# Connectors.net
KiCad netlist of a schematic drawn in Altium Designer
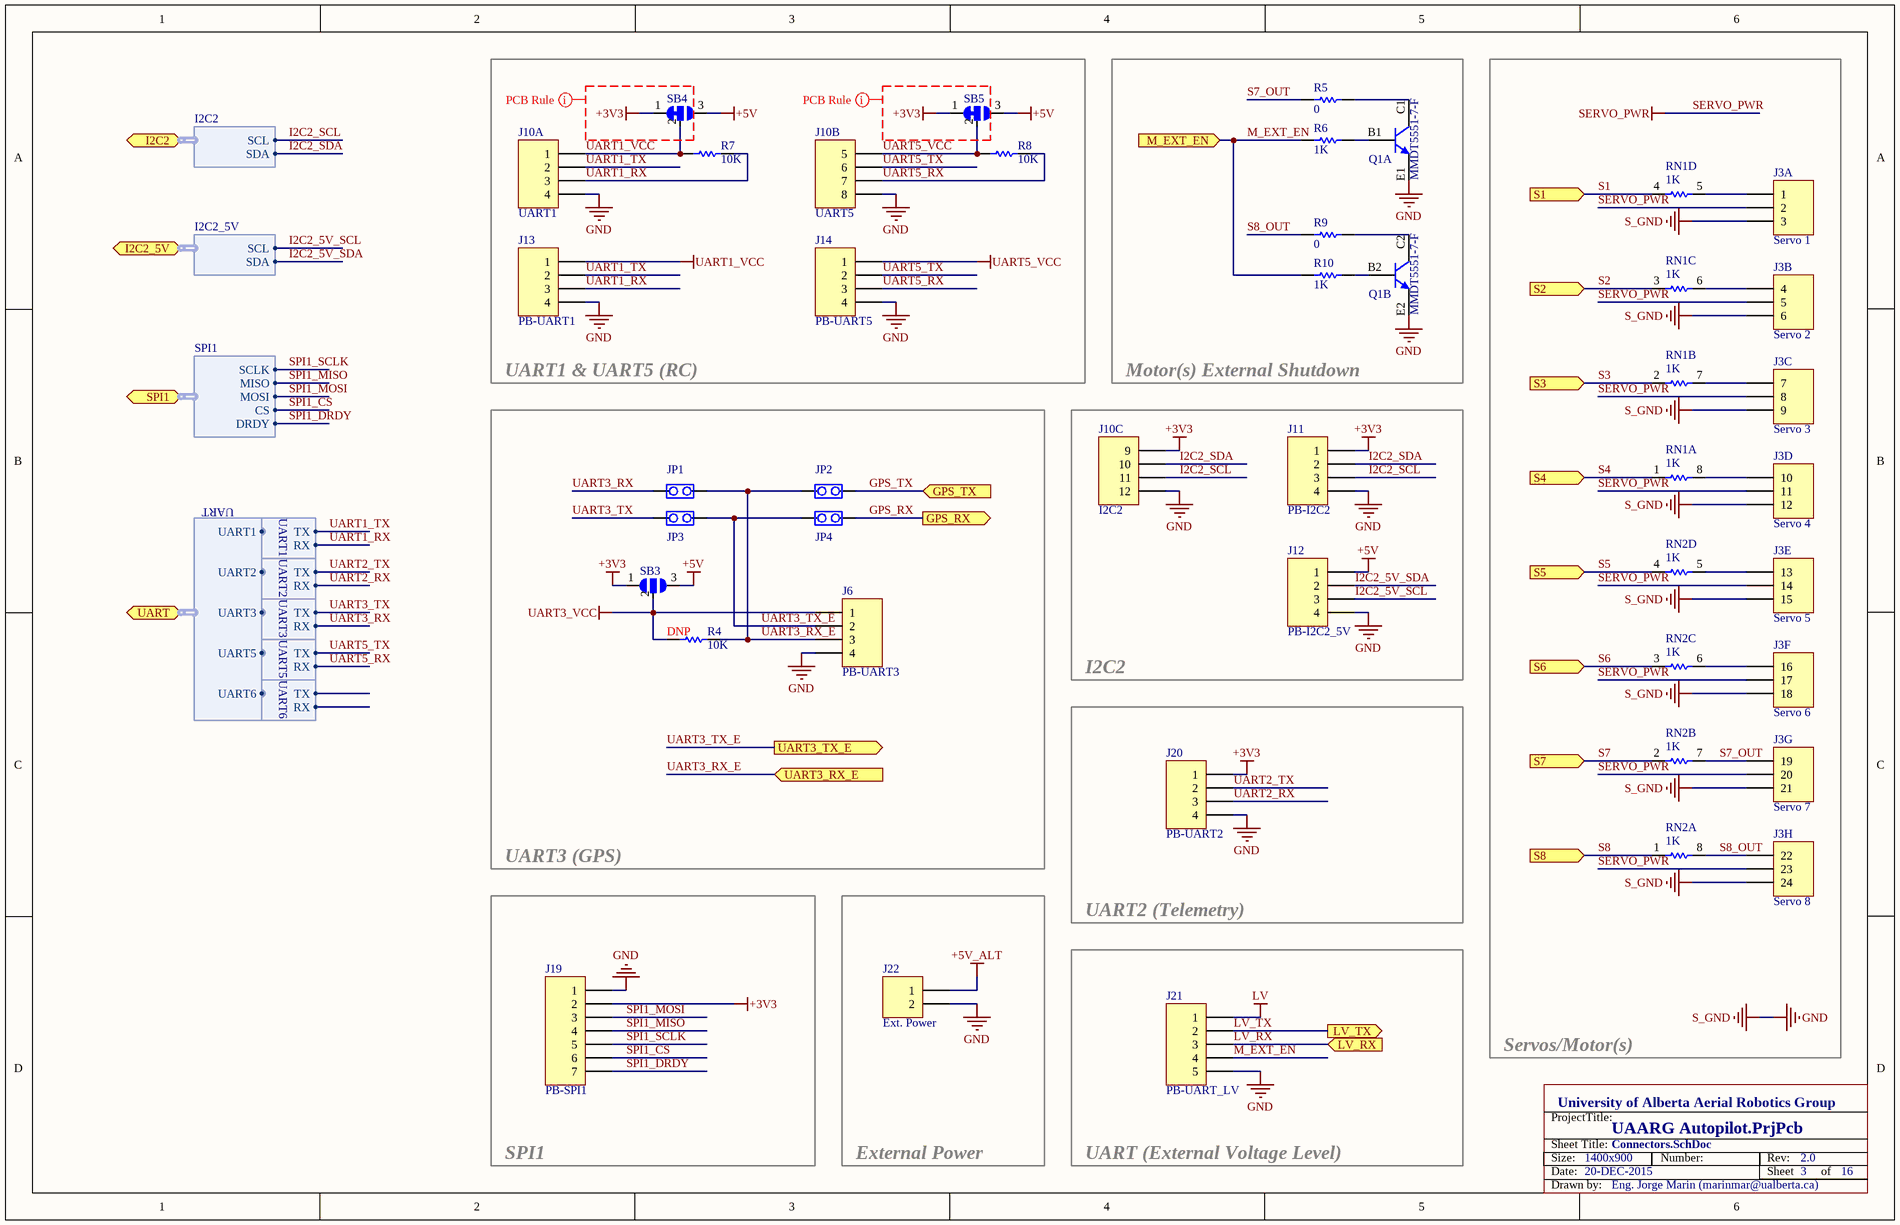
[diagram p0: Connectors.SchDoc]

(export (version "E")
  (design (tool "Eeschema 10.0.6"))
  (components
    (comp (ref "J3")
      (value "Servo")
      (footprint "HDR_3x08_RA")
      (description "Header, 24-Pin")
      (libsource (lib "UAARG Autopilot") (part "Header 3X08 RA"))
    )
    (comp (ref "J6")
      (value "PB-UART3")
      (footprint "PICOBLADE_1X04_VERT_SMD")
      (description "Header, 4-Pin")
      (fields
        (field (name "MANUFACTURER") "Molex, LLC")
        (field (name "MANUFACTURER PART NUMBER") "0533980471")
      )
      (libsource (lib "") (part "Header 4_1"))
    )
    (comp (ref "J10")
      (value "Header")
      (footprint "HDR_3x04_RA")
      (description "Header, 12-Pin")
      (libsource (lib "UAARG Autopilot") (part "Header 3X04 RA"))
    )
    (comp (ref "J11")
      (value "PB-I2C2")
      (footprint "PICOBLADE_1X04_VERT_SMD")
      (description "Header, 4-Pin")
      (fields
        (field (name "MANUFACTURER") "Molex, LLC")
        (field (name "MANUFACTURER PART NUMBER") "0533980471")
      )
      (libsource (lib "Miscellaneous Connectors") (part "Header 4"))
    )
    (comp (ref "J12")
      (value "PB-I2C2_5V")
      (footprint "PICOBLADE_1X04_VERT_SMD")
      (description "Header, 4-Pin")
      (fields
        (field (name "MANUFACTURER") "Molex, LLC")
        (field (name "MANUFACTURER PART NUMBER") "0533980471")
      )
      (libsource (lib "Miscellaneous Connectors") (part "Header 4"))
    )
    (comp (ref "J13")
      (value "PB-UART1")
      (footprint "PICOBLADE_1X04_VERT_SMD")
      (description "Header, 4-Pin")
      (fields
        (field (name "MANUFACTURER") "Molex, LLC")
        (field (name "MANUFACTURER PART NUMBER") "0533980471")
      )
      (libsource (lib "Miscellaneous Connectors") (part "Header 4"))
    )
    (comp (ref "J14")
      (value "PB-UART5")
      (footprint "PICOBLADE_1X04_VERT_SMD")
      (description "Header, 4-Pin")
      (fields
        (field (name "MANUFACTURER") "Molex, LLC")
        (field (name "MANUFACTURER PART NUMBER") "0533980471")
      )
      (libsource (lib "Miscellaneous Connectors") (part "Header 4"))
    )
    (comp (ref "J19")
      (value "PB-SPI1")
      (footprint "PICOBLADE_1X07_VERT_SMD")
      (description "Header, 7-Pin")
      (fields
        (field (name "MANUFACTURER") "Molex, LLC")
        (field (name "MANUFACTURER PART NUMBER") "0533980771")
      )
      (libsource (lib "Miscellaneous Connectors") (part "Header 7"))
    )
    (comp (ref "J20")
      (value "PB-UART2")
      (footprint "PICOBLADE_1X04_VERT_SMD")
      (description "Header, 4-Pin")
      (fields
        (field (name "MANUFACTURER") "Molex, LLC")
        (field (name "MANUFACTURER PART NUMBER") "0533980471")
      )
      (libsource (lib "Miscellaneous Connectors") (part "Header 4"))
    )
    (comp (ref "J21")
      (value "PB-UART_LV")
      (footprint "PICOBLADE_1X05_VERT_SMD")
      (description "Header, 5-Pin")
      (fields
        (field (name "MANUFACTURER PART NUMBER") "0533980571")
        (field (name "MANUFACTURER") "Molex, LLC")
      )
      (libsource (lib "Miscellaneous Connectors") (part "Header 5"))
    )
    (comp (ref "J22")
      (value "Ext. Power")
      (footprint "HDR_1x02")
      (description "Header, 2-Pin")
      (libsource (lib "Miscellaneous Connectors") (part "Header 2"))
    )
    (comp (ref "JP1") (value "Jumper") (footprint "HDR_1x02_JMP") (libsource (lib "") (part "Jumper_1")))
    (comp (ref "JP2")
      (value "Jumper")
      (footprint "HDR_1x02_JMP")
      (libsource (lib "UAARG Autopilot") (part "Jumper"))
    )
    (comp (ref "JP3") (value "Jumper") (footprint "HDR_1x02_JMP") (libsource (lib "") (part "Jumper_1")))
    (comp (ref "JP4")
      (value "Jumper")
      (footprint "HDR_1x02_JMP")
      (libsource (lib "UAARG Autopilot") (part "Jumper"))
    )
    (comp (ref "Q1")
      (value "BJT NPN DUAL")
      (footprint "SOT363-6")
      (description "NPN General Purpose Amplifier")
      (fields
        (field (name "MANUFACTURER PART NUMBER") "MMDT5551-7-F")
        (field (name "MANUFACTURER") "Diodes Incorporated")
      )
      (libsource (lib "UAARG Autopilot") (part "BJT NPN DUAL"))
    )
    (comp (ref "R4")
      (value "10K")
      (footprint "RES_0402[1005M]")
      (description "Resistor")
      (fields
        (field (name "MANUFACTURER") "Yageo")
        (field (name "MANUFACTURER PART NUMBER") "RC0402FR-0710KL")
        (field (name "NOTE") "DNP")
      )
      (libsource (lib "UAARG Autopilot") (part "RES"))
    )
    (comp (ref "R5")
      (value "0")
      (footprint "JUMPER_RES_0402")
      (description "Resistor")
      (fields
        (field (name "MANUFACTURER PART NUMBER") "RC0402JR-070RL")
        (field (name "MANUFACTURER") "Yageo")
      )
      (libsource (lib "UAARG Autopilot") (part "RES"))
    )
    (comp (ref "R6")
      (value "1K")
      (footprint "RES_0402[1005M]")
      (description "Resistor")
      (fields
        (field (name "MANUFACTURER") "Yageo")
        (field (name "MANUFACTURER PART NUMBER") "RC0402FR-071KL")
      )
      (libsource (lib "UAARG Autopilot") (part "RES"))
    )
    (comp (ref "R7")
      (value "10K")
      (footprint "RES_0402[1005M]")
      (description "Resistor")
      (fields
        (field (name "MANUFACTURER") "Yageo")
        (field (name "MANUFACTURER PART NUMBER") "RC0402FR-0710KL")
      )
      (libsource (lib "UAARG Autopilot") (part "RES"))
    )
    (comp (ref "R8")
      (value "10K")
      (footprint "RES_0402[1005M]")
      (description "Resistor")
      (fields
        (field (name "MANUFACTURER") "Yageo")
        (field (name "MANUFACTURER PART NUMBER") "RC0402FR-0710KL")
      )
      (libsource (lib "UAARG Autopilot") (part "RES"))
    )
    (comp (ref "R9")
      (value "0")
      (footprint "JUMPER_RES_0402")
      (description "Resistor")
      (fields
        (field (name "MANUFACTURER PART NUMBER") "RC0402JR-070RL")
        (field (name "MANUFACTURER") "Yageo")
      )
      (libsource (lib "UAARG Autopilot") (part "RES"))
    )
    (comp (ref "R10")
      (value "1K")
      (footprint "RES_0402[1005M]")
      (description "Resistor")
      (fields
        (field (name "MANUFACTURER") "Yageo")
        (field (name "MANUFACTURER PART NUMBER") "RC0402FR-071KL")
      )
      (libsource (lib "UAARG Autopilot") (part "RES"))
    )
    (comp (ref "RN1")
      (value "1K")
      (footprint "RES ARRAY SMD")
      (description "Isolated Resistor Network")
      (fields
        (field (name "MANUFACTURER PART NUMBER") "YC164-JR-071KL")
        (field (name "MANUFACTURER") "Yageo")
      )
      (libsource (lib "UAARG Autopilot") (part "Res Network 1"))
    )
    (comp (ref "RN2")
      (value "1K")
      (footprint "RES ARRAY SMD")
      (description "Isolated Resistor Network")
      (fields
        (field (name "MANUFACTURER PART NUMBER") "YC164-JR-071KL")
        (field (name "MANUFACTURER") "Yageo")
      )
      (libsource (lib "UAARG Autopilot") (part "Res Network 1"))
    )
    (comp (ref "SB3")
      (value "SMD Jumper 1")
      (footprint "SMD JUMPER 1")
      (description "SMD Jumper 3 positions. Open")
      (libsource (lib "UAARG Autopilot") (part "SMD Jumper 1"))
    )
    (comp (ref "SB4")
      (value "SMD Jumper 2")
      (footprint "SMD JUMPER 2")
      (description "SMD Jumper 3 positions. Closed")
      (libsource (lib "UAARG Autopilot") (part "SMD Jumper 2"))
    )
    (comp (ref "SB5")
      (value "SMD Jumper 2")
      (footprint "SMD JUMPER 2")
      (description "SMD Jumper 3 positions. Closed")
      (libsource (lib "UAARG Autopilot") (part "SMD Jumper 2"))
    )
  )
  (nets
    (net (code "5") (name "+3V3") (class "Default")
      (node (ref "J10") (pin "9") (pinfunction "9_9") (pintype "passive"))
      (node (ref "J11") (pin "1") (pinfunction "1_1") (pintype "passive"))
      (node (ref "J19") (pin "2") (pinfunction "2_2") (pintype "passive"))
      (node (ref "J20") (pin "1") (pinfunction "1_1") (pintype "passive"))
      (node (ref "SB3") (pin "1") (pinfunction "1_1") (pintype "passive"))
      (node (ref "SB4") (pin "1") (pinfunction "1_1") (pintype "passive"))
      (node (ref "SB5") (pin "1") (pinfunction "1_1") (pintype "passive"))
    )
    (net (code "6") (name "+5V") (class "Default")
      (node (ref "J12") (pin "1") (pinfunction "1_1") (pintype "passive"))
      (node (ref "SB3") (pin "3") (pinfunction "3_3") (pintype "passive"))
      (node (ref "SB4") (pin "3") (pinfunction "3_3") (pintype "passive"))
      (node (ref "SB5") (pin "3") (pinfunction "3_3") (pintype "passive"))
    )
    (net (code "7") (name "+5V_ALT") (class "Default")
      (node (ref "J22") (pin "1") (pinfunction "1_1") (pintype "passive"))
    )
    (net (code "8") (name "/GPS_RX") (class "Default")
      (node (ref "JP4") (pin "1") (pinfunction "1_1") (pintype "passive"))
    )
    (net (code "9") (name "/GPS_TX") (class "Default")
      (node (ref "JP2") (pin "1") (pinfunction "1_1") (pintype "passive"))
    )
    (net (code "10") (name "/I2C2_5V_SCL") (class "Default")
      (node (ref "J12") (pin "3") (pinfunction "3_3") (pintype "passive"))
    )
    (net (code "11") (name "/I2C2_5V_SDA") (class "Default")
      (node (ref "J12") (pin "2") (pinfunction "2_2") (pintype "passive"))
    )
    (net (code "12") (name "/I2C2_SCL") (class "Default")
      (node (ref "J10") (pin "11") (pinfunction "11_11") (pintype "passive"))
      (node (ref "J11") (pin "3") (pinfunction "3_3") (pintype "passive"))
    )
    (net (code "13") (name "/I2C2_SDA") (class "Default")
      (node (ref "J10") (pin "10") (pinfunction "10_10") (pintype "passive"))
      (node (ref "J11") (pin "2") (pinfunction "2_2") (pintype "passive"))
    )
    (net (code "14") (name "/LV_RX") (class "Default")
      (node (ref "J21") (pin "3") (pinfunction "3_3") (pintype "passive"))
    )
    (net (code "15") (name "/LV_TX") (class "Default")
      (node (ref "J21") (pin "2") (pinfunction "2_2") (pintype "passive"))
    )
    (net (code "16") (name "/M_EXT_EN") (class "Default")
      (node (ref "J21") (pin "4") (pinfunction "4_4") (pintype "passive"))
      (node (ref "R10") (pin "2") (pinfunction "2_2") (pintype "passive"))
      (node (ref "R6") (pin "2") (pinfunction "2_2") (pintype "passive"))
    )
    (net (code "17") (name "/S1") (class "Default")
      (node (ref "RN1") (pin "4") (pinfunction "4_4") (pintype "passive"))
    )
    (net (code "18") (name "/S2") (class "Default")
      (node (ref "RN1") (pin "3") (pinfunction "3_3") (pintype "passive"))
    )
    (net (code "19") (name "/S3") (class "Default")
      (node (ref "RN1") (pin "2") (pinfunction "2_2") (pintype "passive"))
    )
    (net (code "20") (name "/S4") (class "Default")
      (node (ref "RN1") (pin "1") (pinfunction "1_1") (pintype "passive"))
    )
    (net (code "21") (name "/S5") (class "Default")
      (node (ref "RN2") (pin "4") (pinfunction "4_4") (pintype "passive"))
    )
    (net (code "22") (name "/S6") (class "Default")
      (node (ref "RN2") (pin "3") (pinfunction "3_3") (pintype "passive"))
    )
    (net (code "23") (name "/S7") (class "Default")
      (node (ref "RN2") (pin "2") (pinfunction "2_2") (pintype "passive"))
    )
    (net (code "24") (name "/S7_OUT") (class "Default")
      (node (ref "J3") (pin "19") (pinfunction "19_19") (pintype "passive"))
      (node (ref "R5") (pin "2") (pinfunction "2_2") (pintype "passive"))
      (node (ref "RN2") (pin "7") (pinfunction "7_7") (pintype "passive"))
    )
    (net (code "25") (name "/S8") (class "Default")
      (node (ref "RN2") (pin "1") (pinfunction "1_1") (pintype "passive"))
    )
    (net (code "26") (name "/S8_OUT") (class "Default")
      (node (ref "J3") (pin "22") (pinfunction "22_22") (pintype "passive"))
      (node (ref "R9") (pin "2") (pinfunction "2_2") (pintype "passive"))
      (node (ref "RN2") (pin "8") (pinfunction "8_8") (pintype "passive"))
    )
    (net (code "27") (name "/SPI1_CS") (class "Default")
      (node (ref "J19") (pin "6") (pinfunction "6_6") (pintype "passive"))
    )
    (net (code "28") (name "/SPI1_DRDY") (class "Default")
      (node (ref "J19") (pin "7") (pinfunction "7_7") (pintype "passive"))
    )
    (net (code "29") (name "/SPI1_MISO") (class "Default")
      (node (ref "J19") (pin "4") (pinfunction "4_4") (pintype "passive"))
    )
    (net (code "30") (name "/SPI1_MOSI") (class "Default")
      (node (ref "J19") (pin "3") (pinfunction "3_3") (pintype "passive"))
    )
    (net (code "31") (name "/SPI1_SCLK") (class "Default")
      (node (ref "J19") (pin "5") (pinfunction "5_5") (pintype "passive"))
    )
    (net (code "32") (name "/UART1_RX") (class "Default")
      (node (ref "J10") (pin "3") (pinfunction "3_3") (pintype "passive"))
      (node (ref "J13") (pin "3") (pinfunction "3_3") (pintype "passive"))
      (node (ref "R7") (pin "1") (pinfunction "1_1") (pintype "passive"))
    )
    (net (code "33") (name "/UART1_TX") (class "Default")
      (node (ref "J10") (pin "2") (pinfunction "2_2") (pintype "passive"))
      (node (ref "J13") (pin "2") (pinfunction "2_2") (pintype "passive"))
    )
    (net (code "34") (name "/UART2_RX") (class "Default")
      (node (ref "J20") (pin "3") (pinfunction "3_3") (pintype "passive"))
    )
    (net (code "35") (name "/UART2_TX") (class "Default")
      (node (ref "J20") (pin "2") (pinfunction "2_2") (pintype "passive"))
    )
    (net (code "36") (name "/UART3_RX") (class "Default")
      (node (ref "JP1") (pin "1") (pinfunction "1_1") (pintype "passive"))
    )
    (net (code "37") (name "/UART3_RX_E") (class "Default")
      (node (ref "J6") (pin "3") (pinfunction "3_3") (pintype "passive"))
      (node (ref "JP1") (pin "2") (pinfunction "2_2") (pintype "passive"))
      (node (ref "JP2") (pin "2") (pinfunction "2_2") (pintype "passive"))
      (node (ref "R4") (pin "1") (pinfunction "1_1") (pintype "passive"))
    )
    (net (code "38") (name "/UART3_TX") (class "Default")
      (node (ref "JP3") (pin "1") (pinfunction "1_1") (pintype "passive"))
    )
    (net (code "39") (name "/UART3_TX_E") (class "Default")
      (node (ref "J6") (pin "2") (pinfunction "2_2") (pintype "passive"))
      (node (ref "JP3") (pin "2") (pinfunction "2_2") (pintype "passive"))
      (node (ref "JP4") (pin "2") (pinfunction "2_2") (pintype "passive"))
    )
    (net (code "40") (name "/UART5_RX") (class "Default")
      (node (ref "J10") (pin "7") (pinfunction "7_7") (pintype "passive"))
      (node (ref "J14") (pin "3") (pinfunction "3_3") (pintype "passive"))
      (node (ref "R8") (pin "1") (pinfunction "1_1") (pintype "passive"))
    )
    (net (code "41") (name "/UART5_TX") (class "Default")
      (node (ref "J10") (pin "6") (pinfunction "6_6") (pintype "passive"))
      (node (ref "J14") (pin "2") (pinfunction "2_2") (pintype "passive"))
    )
    (net (code "46") (name "GND") (class "Default")
      (node (ref "J10") (pin "12") (pinfunction "12_12") (pintype "passive"))
      (node (ref "J10") (pin "4") (pinfunction "4_4") (pintype "passive"))
      (node (ref "J10") (pin "8") (pinfunction "8_8") (pintype "passive"))
      (node (ref "J11") (pin "4") (pinfunction "4_4") (pintype "passive"))
      (node (ref "J12") (pin "4") (pinfunction "4_4") (pintype "passive"))
      (node (ref "J13") (pin "4") (pinfunction "4_4") (pintype "passive"))
      (node (ref "J14") (pin "4") (pinfunction "4_4") (pintype "passive"))
      (node (ref "J19") (pin "1") (pinfunction "1_1") (pintype "passive"))
      (node (ref "J20") (pin "4") (pinfunction "4_4") (pintype "passive"))
      (node (ref "J21") (pin "5") (pinfunction "5_5") (pintype "passive"))
      (node (ref "J22") (pin "2") (pinfunction "2_2") (pintype "passive"))
      (node (ref "J3") (pin "12") (pinfunction "12_12") (pintype "passive"))
      (node (ref "J3") (pin "15") (pinfunction "15_15") (pintype "passive"))
      (node (ref "J3") (pin "18") (pinfunction "18_18") (pintype "passive"))
      (node (ref "J3") (pin "21") (pinfunction "21_21") (pintype "passive"))
      (node (ref "J3") (pin "24") (pinfunction "24_24") (pintype "passive"))
      (node (ref "J3") (pin "3") (pinfunction "3_3") (pintype "passive"))
      (node (ref "J3") (pin "6") (pinfunction "6_6") (pintype "passive"))
      (node (ref "J3") (pin "9") (pinfunction "9_9") (pintype "passive"))
      (node (ref "J6") (pin "4") (pinfunction "4_4") (pintype "passive"))
      (node (ref "Q1") (pin "E1") (pinfunction "E1_E1") (pintype "passive"))
      (node (ref "Q1") (pin "E2") (pinfunction "E2_E2") (pintype "passive"))
    )
    (net (code "47") (name "LV") (class "Default")
      (node (ref "J21") (pin "1") (pinfunction "1_1") (pintype "passive"))
    )
    (net (code "48") (name "Net-(J3-Pad1)") (class "Default")
      (node (ref "J3") (pin "1") (pinfunction "1_1") (pintype "passive"))
      (node (ref "RN1") (pin "5") (pinfunction "5_5") (pintype "passive"))
    )
    (net (code "49") (name "Net-(J3-Pad4)") (class "Default")
      (node (ref "J3") (pin "4") (pinfunction "4_4") (pintype "passive"))
      (node (ref "RN1") (pin "6") (pinfunction "6_6") (pintype "passive"))
    )
    (net (code "50") (name "Net-(J3-Pad7)") (class "Default")
      (node (ref "J3") (pin "7") (pinfunction "7_7") (pintype "passive"))
      (node (ref "RN1") (pin "7") (pinfunction "7_7") (pintype "passive"))
    )
    (net (code "51") (name "Net-(J3-Pad10)") (class "Default")
      (node (ref "J3") (pin "10") (pinfunction "10_10") (pintype "passive"))
      (node (ref "RN1") (pin "8") (pinfunction "8_8") (pintype "passive"))
    )
    (net (code "52") (name "Net-(J3-Pad13)") (class "Default")
      (node (ref "J3") (pin "13") (pinfunction "13_13") (pintype "passive"))
      (node (ref "RN2") (pin "5") (pinfunction "5_5") (pintype "passive"))
    )
    (net (code "53") (name "Net-(J3-Pad16)") (class "Default")
      (node (ref "J3") (pin "16") (pinfunction "16_16") (pintype "passive"))
      (node (ref "RN2") (pin "6") (pinfunction "6_6") (pintype "passive"))
    )
    (net (code "54") (name "Net-(Q1-PadB1)") (class "Default")
      (node (ref "Q1") (pin "B1") (pinfunction "B1_B1") (pintype "passive"))
      (node (ref "R6") (pin "1") (pinfunction "1_1") (pintype "passive"))
    )
    (net (code "55") (name "Net-(Q1-PadB2)") (class "Default")
      (node (ref "Q1") (pin "B2") (pinfunction "B2_B2") (pintype "passive"))
      (node (ref "R10") (pin "1") (pinfunction "1_1") (pintype "passive"))
    )
    (net (code "56") (name "Net-(Q1-PadC1)") (class "Default")
      (node (ref "Q1") (pin "C1") (pinfunction "C1_C1") (pintype "passive"))
      (node (ref "R5") (pin "1") (pinfunction "1_1") (pintype "passive"))
    )
    (net (code "57") (name "Net-(Q1-PadC2)") (class "Default")
      (node (ref "Q1") (pin "C2") (pinfunction "C2_C2") (pintype "passive"))
      (node (ref "R9") (pin "1") (pinfunction "1_1") (pintype "passive"))
    )
    (net (code "58") (name "SERVO_PWR") (class "Default")
      (node (ref "J3") (pin "11") (pinfunction "11_11") (pintype "passive"))
      (node (ref "J3") (pin "14") (pinfunction "14_14") (pintype "passive"))
      (node (ref "J3") (pin "17") (pinfunction "17_17") (pintype "passive"))
      (node (ref "J3") (pin "2") (pinfunction "2_2") (pintype "passive"))
      (node (ref "J3") (pin "20") (pinfunction "20_20") (pintype "passive"))
      (node (ref "J3") (pin "23") (pinfunction "23_23") (pintype "passive"))
      (node (ref "J3") (pin "5") (pinfunction "5_5") (pintype "passive"))
      (node (ref "J3") (pin "8") (pinfunction "8_8") (pintype "passive"))
    )
    (net (code "59") (name "UART1_VCC") (class "Default")
      (node (ref "J10") (pin "1") (pinfunction "1_1") (pintype "passive"))
      (node (ref "J13") (pin "1") (pinfunction "1_1") (pintype "passive"))
      (node (ref "R7") (pin "2") (pinfunction "2_2") (pintype "passive"))
      (node (ref "SB4") (pin "2") (pinfunction "2_2") (pintype "passive"))
    )
    (net (code "60") (name "UART3_VCC") (class "Default")
      (node (ref "J6") (pin "1") (pinfunction "1_1") (pintype "passive"))
      (node (ref "R4") (pin "2") (pinfunction "2_2") (pintype "passive"))
      (node (ref "SB3") (pin "2") (pinfunction "2_2") (pintype "passive"))
    )
    (net (code "61") (name "UART5_VCC") (class "Default")
      (node (ref "J10") (pin "5") (pinfunction "5_5") (pintype "passive"))
      (node (ref "J14") (pin "1") (pinfunction "1_1") (pintype "passive"))
      (node (ref "R8") (pin "2") (pinfunction "2_2") (pintype "passive"))
      (node (ref "SB5") (pin "2") (pinfunction "2_2") (pintype "passive"))
    )
  )
)
